# ACC.net
KiCad netlist of a schematic drawn in EAGLE
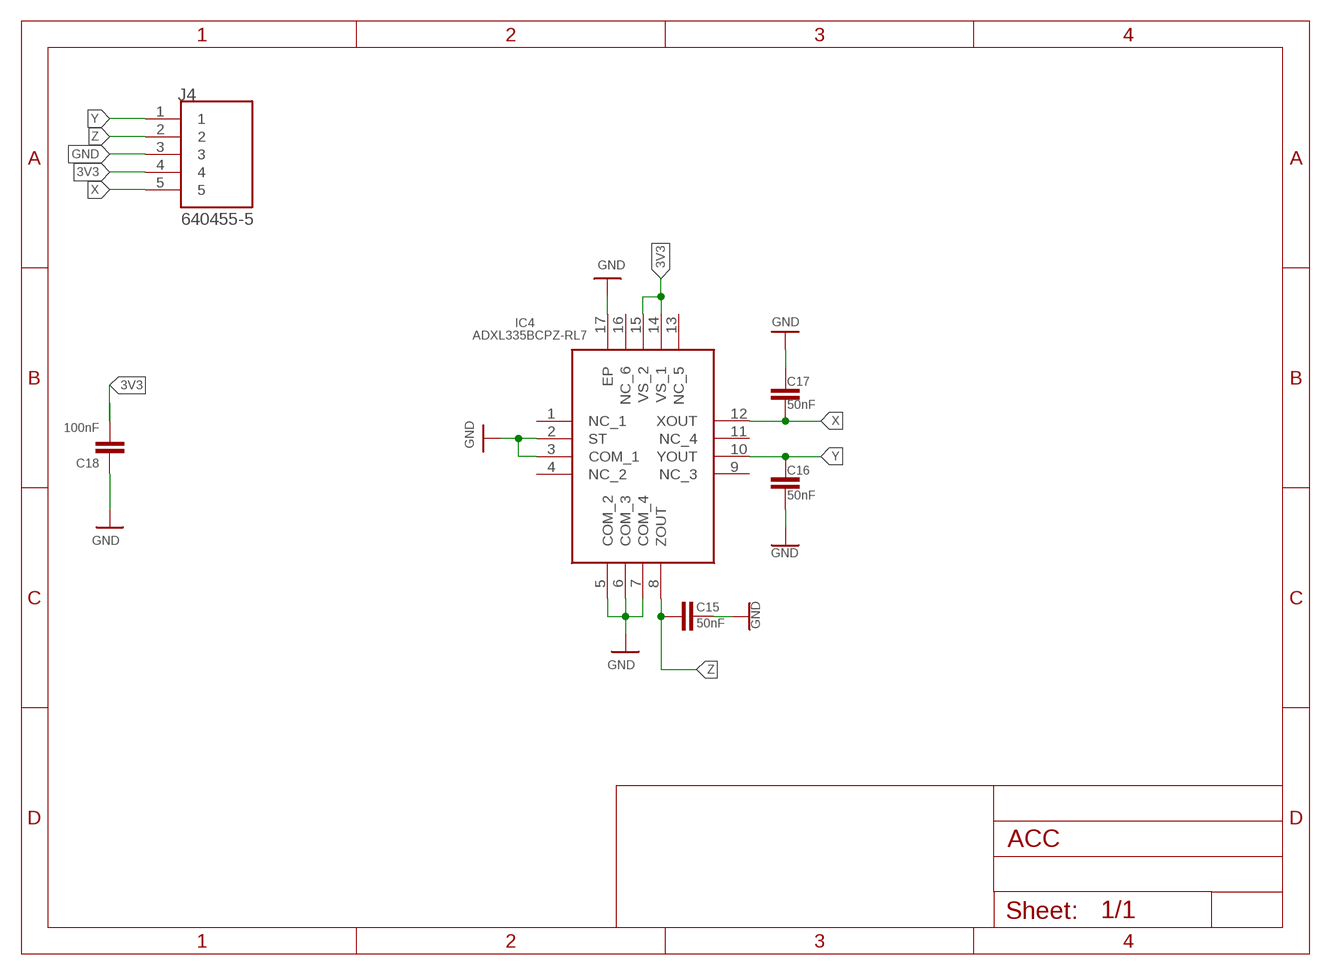
[diagram p0: schematic, sheet 1]

(export (version "E")
  (design (tool "Eeschema 10.0.6"))
  (components
    (comp (ref "C15")
      (value "50nF")
      (footprint "eagle-import:C0603")
      (libsource (lib "eagle-import") (part "C-EUC0603"))
    )
    (comp (ref "C16")
      (value "50nF")
      (footprint "eagle-import:C0603")
      (libsource (lib "eagle-import") (part "C-EUC0603"))
    )
    (comp (ref "C17")
      (value "50nF")
      (footprint "eagle-import:C0603")
      (libsource (lib "eagle-import") (part "C-EUC0603"))
    )
    (comp (ref "C18")
      (value "100nF")
      (footprint "eagle-import:C0603")
      (libsource (lib "eagle-import") (part "C-EUC0603"))
    )
    (comp (ref "IC4")
      (value "ADXL335BCPZ-RL7")
      (footprint "eagle-import:QFN65P400X400X150-17N")
      (fields (field (name "MOUSER_PART_NUMBER") "584-ADXL335BCPZ-R7"))
      (libsource (lib "eagle-import") (part "ADXL335BCPZ-RL7"))
    )
    (comp (ref "J4")
      (value "640455-5")
      (footprint "eagle-import:TE_640455-5")
      (fields (field (name "DIGI-KEY_PART_NUMBER") "A19453-ND") (field (name "MF") "TE Connectivity"))
      (libsource (lib "eagle-import") (part "640455-5"))
    )
  )
  (nets
    (net (code "1") (name "3V3") (class "Default")
      (node (ref "C18") (pin "2") (pinfunction "2_2") (pintype "passive"))
      (node (ref "IC4") (pin "14") (pinfunction "VS_1_14") (pintype "bidirectional"))
      (node (ref "IC4") (pin "15") (pinfunction "VS_2_15") (pintype "bidirectional"))
      (node (ref "J4") (pin "4") (pinfunction "4_4") (pintype "passive"))
    )
    (net (code "2") (name "GND") (class "Default")
      (node (ref "C15") (pin "1") (pinfunction "1_1") (pintype "passive"))
      (node (ref "C16") (pin "2") (pinfunction "2_2") (pintype "passive"))
      (node (ref "C17") (pin "1") (pinfunction "1_1") (pintype "passive"))
      (node (ref "C18") (pin "1") (pinfunction "1_1") (pintype "passive"))
      (node (ref "IC4") (pin "17") (pinfunction "EP_17") (pintype "bidirectional"))
      (node (ref "IC4") (pin "2") (pinfunction "ST_2") (pintype "bidirectional"))
      (node (ref "IC4") (pin "3") (pinfunction "COM_1_3") (pintype "bidirectional"))
      (node (ref "IC4") (pin "5") (pinfunction "COM_2_5") (pintype "bidirectional"))
      (node (ref "IC4") (pin "6") (pinfunction "COM_3_6") (pintype "bidirectional"))
      (node (ref "IC4") (pin "7") (pinfunction "COM_4_7") (pintype "bidirectional"))
      (node (ref "J4") (pin "3") (pinfunction "3_3") (pintype "passive"))
    )
    (net (code "3") (name "X") (class "Default")
      (node (ref "C17") (pin "2") (pinfunction "2_2") (pintype "passive"))
      (node (ref "IC4") (pin "12") (pinfunction "XOUT_12") (pintype "bidirectional"))
      (node (ref "J4") (pin "5") (pinfunction "5_5") (pintype "passive"))
    )
    (net (code "4") (name "Y") (class "Default")
      (node (ref "C16") (pin "1") (pinfunction "1_1") (pintype "passive"))
      (node (ref "IC4") (pin "10") (pinfunction "YOUT_10") (pintype "bidirectional"))
      (node (ref "J4") (pin "1") (pinfunction "1_1") (pintype "passive"))
    )
    (net (code "5") (name "Z") (class "Default")
      (node (ref "C15") (pin "2") (pinfunction "2_2") (pintype "passive"))
      (node (ref "IC4") (pin "8") (pinfunction "ZOUT_8") (pintype "bidirectional"))
      (node (ref "J4") (pin "2") (pinfunction "2_2") (pintype "passive"))
    )
    (net (code "6") (name "unconnected-(IC4-NC_1-Pad1)") (class "Default")
      (node (ref "IC4") (pin "1") (pinfunction "NC_1_1") (pintype "bidirectional"))
    )
    (net (code "7") (name "unconnected-(IC4-NC_2-Pad4)") (class "Default")
      (node (ref "IC4") (pin "4") (pinfunction "NC_2_4") (pintype "bidirectional"))
    )
    (net (code "8") (name "unconnected-(IC4-NC_3-Pad9)") (class "Default")
      (node (ref "IC4") (pin "9") (pinfunction "NC_3_9") (pintype "bidirectional"))
    )
    (net (code "9") (name "unconnected-(IC4-NC_4-Pad11)") (class "Default")
      (node (ref "IC4") (pin "11") (pinfunction "NC_4_11") (pintype "bidirectional"))
    )
    (net (code "10") (name "unconnected-(IC4-NC_5-Pad13)") (class "Default")
      (node (ref "IC4") (pin "13") (pinfunction "NC_5_13") (pintype "bidirectional"))
    )
    (net (code "11") (name "unconnected-(IC4-NC_6-Pad16)") (class "Default")
      (node (ref "IC4") (pin "16") (pinfunction "NC_6_16") (pintype "bidirectional"))
    )
  )
)
